# AD9236.net
KiCad netlist of a schematic drawn in Altium Designer
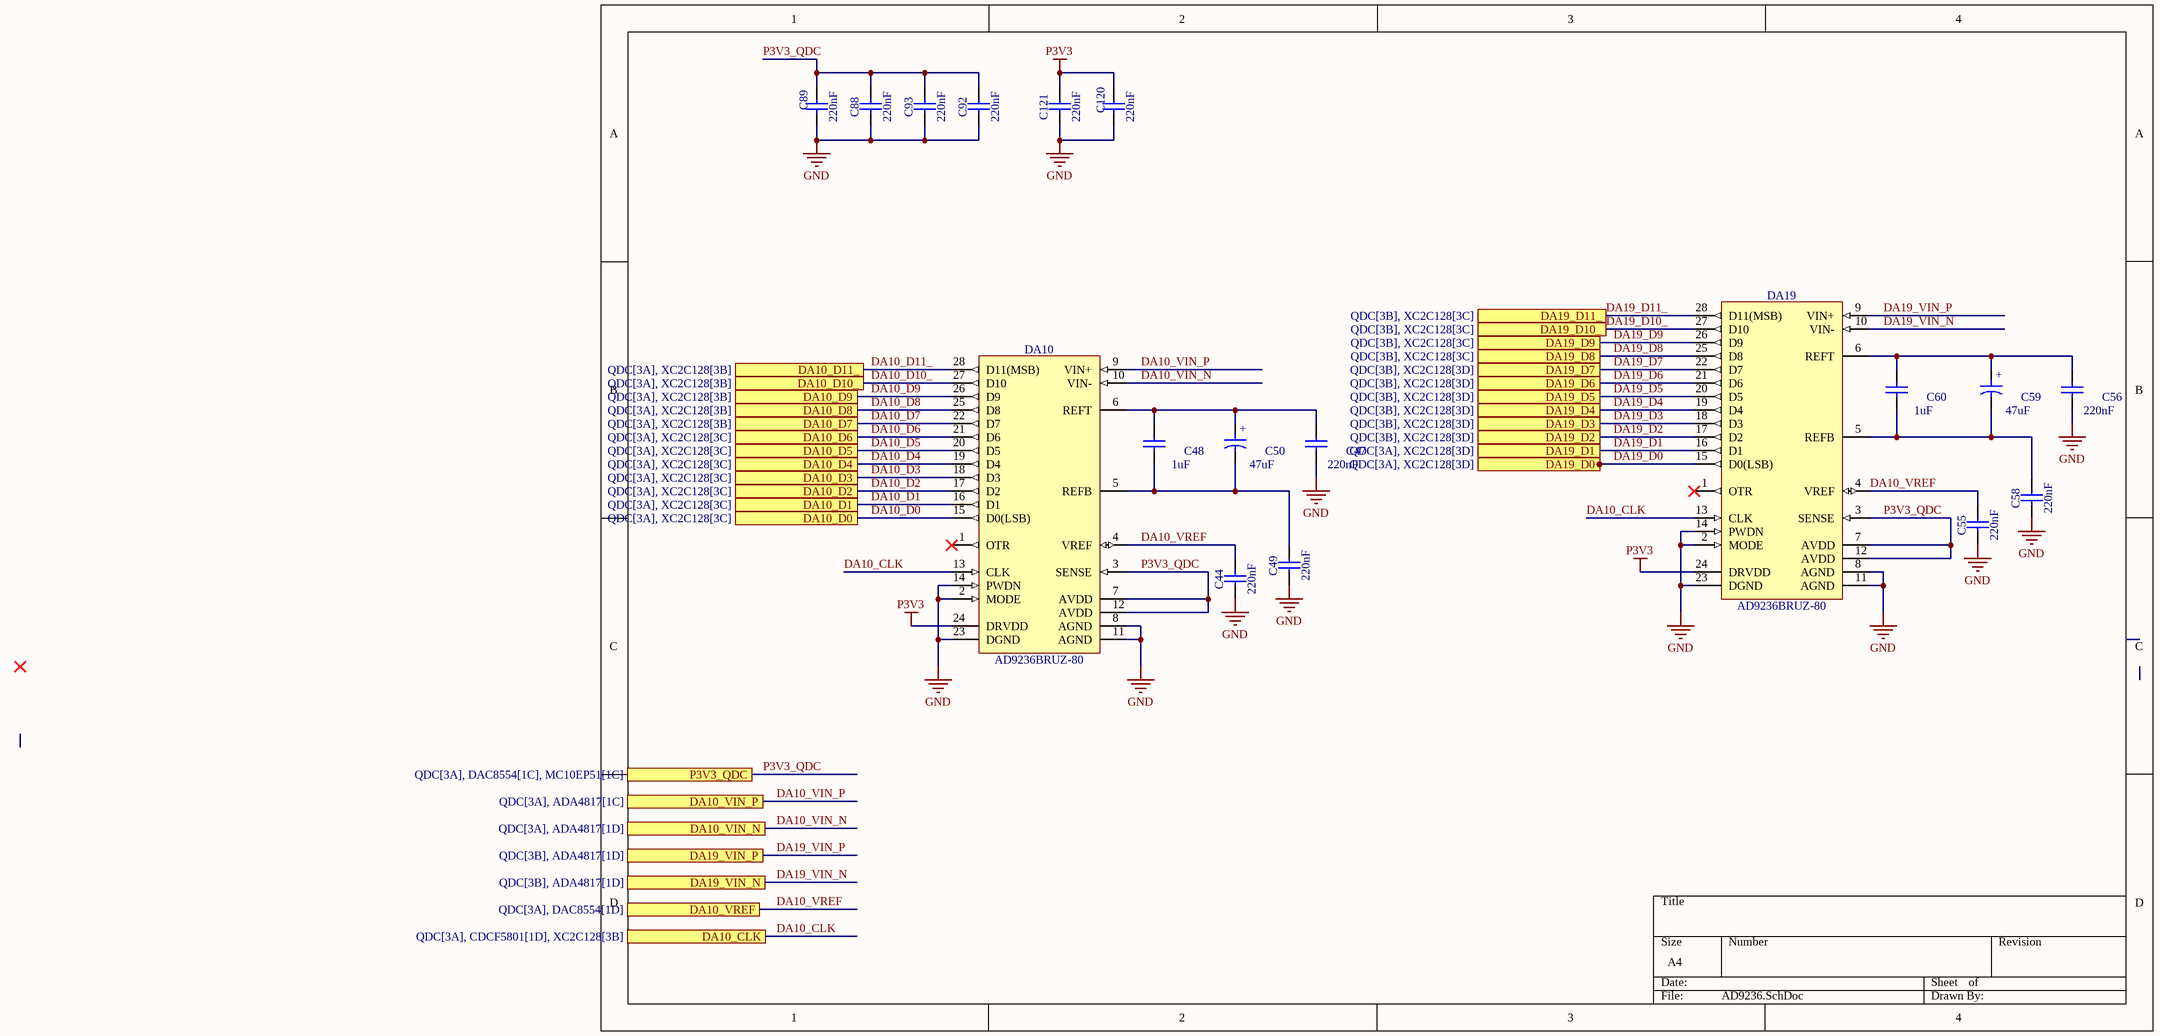
[diagram p0: AD9236.SchDoc]

(export (version "E")
  (design (tool "Eeschema 10.0.6"))
  (components
    (comp (ref "C44")
      (value "220nF")
      (footprint "CAPC2012X135N")
      (description "Non-polarised capacitor")
      (fields
        (field (name "PART NUMBER") "CC0805_220NF_50V_10%_X7R")
        (field (name "VOLTAGE") "50V")
        (field (name "AUTHOR") "CERN DEM JLC")
      )
      (libsource (lib "Capacitors") (part "Capacitor - non polarized"))
    )
    (comp (ref "C47")
      (value "220nF")
      (footprint "CAPC2012X135N")
      (description "Non-polarised capacitor")
      (fields
        (field (name "PART NUMBER") "CC0805_220NF_50V_10%_X7R")
        (field (name "VOLTAGE") "50V")
        (field (name "AUTHOR") "CERN DEM JLC")
      )
      (libsource (lib "Capacitors") (part "Capacitor - non polarized"))
    )
    (comp (ref "C48")
      (value "1uF")
      (footprint "CAPC2012X140N")
      (description "Non-polarised capacitor")
      (fields
        (field (name "PART NUMBER") "CC0805_1UF_25V_10%_X7R")
        (field (name "VOLTAGE") "25V")
        (field (name "AUTHOR") "CERN DEM JLC")
      )
      (libsource (lib "Capacitors") (part "Capacitor - non polarized"))
    )
    (comp (ref "C49")
      (value "220nF")
      (footprint "CAPC2012X135N")
      (description "Non-polarised capacitor")
      (fields
        (field (name "PART NUMBER") "CC0805_220NF_50V_10%_X7R")
        (field (name "VOLTAGE") "50V")
        (field (name "AUTHOR") "CERN DEM JLC")
      )
      (libsource (lib "Capacitors") (part "Capacitor - non polarized"))
    )
    (comp (ref "C50")
      (value "47uF")
      (footprint "CAPMP3528X120N")
      (description "Polarised capacitor")
      (fields
        (field (name "PART NUMBER") "CTE3528-12_47UF_10V_20%_PANASONIC_TPG")
        (field (name "VOLTAGE") "10V")
        (field (name "AUTHOR") "CERN DEM JLC")
      )
      (libsource (lib "Capacitors") (part "Capacitor - polarized"))
    )
    (comp (ref "C55")
      (value "220nF")
      (footprint "CAPC2012X135N")
      (description "Non-polarised capacitor")
      (fields
        (field (name "PART NUMBER") "CC0805_220NF_50V_10%_X7R")
        (field (name "VOLTAGE") "50V")
        (field (name "AUTHOR") "CERN DEM JLC")
      )
      (libsource (lib "Capacitors") (part "Capacitor - non polarized"))
    )
    (comp (ref "C56")
      (value "220nF")
      (footprint "CAPC2012X135N")
      (description "Non-polarised capacitor")
      (fields
        (field (name "PART NUMBER") "CC0805_220NF_50V_10%_X7R")
        (field (name "VOLTAGE") "50V")
        (field (name "AUTHOR") "CERN DEM JLC")
      )
      (libsource (lib "Capacitors") (part "Capacitor - non polarized"))
    )
    (comp (ref "C58")
      (value "220nF")
      (footprint "CAPC2012X135N")
      (description "Non-polarised capacitor")
      (fields
        (field (name "PART NUMBER") "CC0805_220NF_50V_10%_X7R")
        (field (name "VOLTAGE") "50V")
        (field (name "AUTHOR") "CERN DEM JLC")
      )
      (libsource (lib "Capacitors") (part "Capacitor - non polarized"))
    )
    (comp (ref "C59")
      (value "47uF")
      (footprint "CAPMP3528X120N")
      (description "Polarised capacitor")
      (fields
        (field (name "PART NUMBER") "CTE3528-12_47UF_10V_20%_PANASONIC_TPG")
        (field (name "VOLTAGE") "10V")
        (field (name "AUTHOR") "CERN DEM JLC")
      )
      (libsource (lib "Capacitors") (part "Capacitor - polarized"))
    )
    (comp (ref "C60")
      (value "1uF")
      (footprint "CAPC2012X140N")
      (description "Non-polarised capacitor")
      (fields
        (field (name "PART NUMBER") "CC0805_1UF_25V_10%_X7R")
        (field (name "VOLTAGE") "25V")
        (field (name "AUTHOR") "CERN DEM JLC")
      )
      (libsource (lib "Capacitors") (part "Capacitor - non polarized"))
    )
    (comp (ref "C88")
      (value "220nF")
      (footprint "CAPC2012X135N")
      (description "Non-polarised capacitor")
      (fields
        (field (name "PART NUMBER") "CC0805_220NF_50V_10%_X7R")
        (field (name "VOLTAGE") "50V")
        (field (name "AUTHOR") "CERN DEM JLC")
      )
      (libsource (lib "Capacitors") (part "Capacitor - non polarized"))
    )
    (comp (ref "C89")
      (value "220nF")
      (footprint "CAPC2012X135N")
      (description "Non-polarised capacitor")
      (fields
        (field (name "PART NUMBER") "CC0805_220NF_50V_10%_X7R")
        (field (name "VOLTAGE") "50V")
        (field (name "AUTHOR") "CERN DEM JLC")
      )
      (libsource (lib "Capacitors") (part "Capacitor - non polarized"))
    )
    (comp (ref "C92")
      (value "220nF")
      (footprint "CAPC2012X135N")
      (description "Non-polarised capacitor")
      (fields
        (field (name "PART NUMBER") "CC0805_220NF_50V_10%_X7R")
        (field (name "VOLTAGE") "50V")
        (field (name "AUTHOR") "CERN DEM JLC")
      )
      (libsource (lib "Capacitors") (part "Capacitor - non polarized"))
    )
    (comp (ref "C93")
      (value "220nF")
      (footprint "CAPC2012X135N")
      (description "Non-polarised capacitor")
      (fields
        (field (name "PART NUMBER") "CC0805_220NF_50V_10%_X7R")
        (field (name "VOLTAGE") "50V")
        (field (name "AUTHOR") "CERN DEM JLC")
      )
      (libsource (lib "Capacitors") (part "Capacitor - non polarized"))
    )
    (comp (ref "C120")
      (value "220nF")
      (footprint "CAPC2012X135N")
      (description "Non-polarised capacitor")
      (fields
        (field (name "PART NUMBER") "CC0805_220NF_50V_10%_X7R")
        (field (name "VOLTAGE") "50V")
        (field (name "AUTHOR") "CERN DEM JLC")
      )
      (libsource (lib "Capacitors") (part "Capacitor - non polarized"))
    )
    (comp (ref "C121")
      (value "220nF")
      (footprint "CAPC2012X135N")
      (description "Non-polarised capacitor")
      (fields
        (field (name "PART NUMBER") "CC0805_220NF_50V_10%_X7R")
        (field (name "VOLTAGE") "50V")
        (field (name "AUTHOR") "CERN DEM JLC")
      )
      (libsource (lib "Capacitors") (part "Capacitor - non polarized"))
    )
    (comp (ref "DA10")
      (value "AD9236BRUZ-80")
      (footprint "SOP65P640X120-28N")
      (description "12-Bit, 80 MSPS 3 V ADC")
      (fields
        (field (name "MANUFACTURER") "ANALOG DEVICES")
        (field (name "MANUFACTURER PART NUMBER") "AD9235BRUZ-40")
        (field (name "AUTHOR") "CERN DEM HF")
      )
      (libsource (lib "ICs And Semiconductors") (part "AD9236BRU"))
    )
    (comp (ref "DA19")
      (value "AD9236BRUZ-80")
      (footprint "SOP65P640X120-28N")
      (description "12-Bit, 80 MSPS 3 V ADC")
      (fields
        (field (name "MANUFACTURER") "ANALOG DEVICES")
        (field (name "MANUFACTURER PART NUMBER") "AD9235BRUZ-40")
        (field (name "AUTHOR") "CERN DEM HF")
      )
      (libsource (lib "ICs And Semiconductors") (part "AD9236BRU"))
    )
  )
  (nets
    (net (code "1") (name "/DA10_CLK") (class "Default")
      (node (ref "DA10") (pin "13") (pinfunction "CLK_13") (pintype "input"))
      (node (ref "DA19") (pin "13") (pinfunction "CLK_13") (pintype "input"))
    )
    (net (code "2") (name "/DA10_D0") (class "Default")
      (node (ref "DA10") (pin "15") (pinfunction "D0(LSB)_15") (pintype "output"))
    )
    (net (code "3") (name "/DA10_D1") (class "Default")
      (node (ref "DA10") (pin "16") (pinfunction "D1_16") (pintype "output"))
    )
    (net (code "4") (name "/DA10_D2") (class "Default")
      (node (ref "DA10") (pin "17") (pinfunction "D2_17") (pintype "output"))
    )
    (net (code "5") (name "/DA10_D3") (class "Default")
      (node (ref "DA10") (pin "18") (pinfunction "D3_18") (pintype "output"))
    )
    (net (code "6") (name "/DA10_D4") (class "Default")
      (node (ref "DA10") (pin "19") (pinfunction "D4_19") (pintype "output"))
    )
    (net (code "7") (name "/DA10_D5") (class "Default")
      (node (ref "DA10") (pin "20") (pinfunction "D5_20") (pintype "output"))
    )
    (net (code "8") (name "/DA10_D6") (class "Default")
      (node (ref "DA10") (pin "21") (pinfunction "D6_21") (pintype "output"))
    )
    (net (code "9") (name "/DA10_D7") (class "Default")
      (node (ref "DA10") (pin "22") (pinfunction "D7_22") (pintype "output"))
    )
    (net (code "10") (name "/DA10_D8") (class "Default")
      (node (ref "DA10") (pin "25") (pinfunction "D8_25") (pintype "output"))
    )
    (net (code "11") (name "/DA10_D9") (class "Default")
      (node (ref "DA10") (pin "26") (pinfunction "D9_26") (pintype "output"))
    )
    (net (code "12") (name "/DA10_D10_") (class "Default")
      (node (ref "DA10") (pin "27") (pinfunction "D10_27") (pintype "output"))
    )
    (net (code "13") (name "/DA10_D11_") (class "Default")
      (node (ref "DA10") (pin "28") (pinfunction "D11(MSB)_28") (pintype "output"))
    )
    (net (code "14") (name "/DA10_VIN_N") (class "Default")
      (node (ref "DA10") (pin "10") (pinfunction "VIN-_10") (pintype "input"))
    )
    (net (code "15") (name "/DA10_VIN_P") (class "Default")
      (node (ref "DA10") (pin "9") (pinfunction "VIN+_9") (pintype "input"))
    )
    (net (code "16") (name "/DA10_VREF") (class "Default")
      (node (ref "C44") (pin "2") (pinfunction "2_2") (pintype "passive"))
      (node (ref "C55") (pin "2") (pinfunction "2_2") (pintype "passive"))
      (node (ref "DA10") (pin "4") (pinfunction "VREF_4") (pintype "bidirectional"))
      (node (ref "DA19") (pin "4") (pinfunction "VREF_4") (pintype "bidirectional"))
    )
    (net (code "17") (name "/DA19_D0") (class "Default")
      (node (ref "DA19") (pin "15") (pinfunction "D0(LSB)_15") (pintype "output"))
    )
    (net (code "18") (name "/DA19_D1") (class "Default")
      (node (ref "DA19") (pin "16") (pinfunction "D1_16") (pintype "output"))
    )
    (net (code "19") (name "/DA19_D2") (class "Default")
      (node (ref "DA19") (pin "17") (pinfunction "D2_17") (pintype "output"))
    )
    (net (code "20") (name "/DA19_D3") (class "Default")
      (node (ref "DA19") (pin "18") (pinfunction "D3_18") (pintype "output"))
    )
    (net (code "21") (name "/DA19_D4") (class "Default")
      (node (ref "DA19") (pin "19") (pinfunction "D4_19") (pintype "output"))
    )
    (net (code "22") (name "/DA19_D5") (class "Default")
      (node (ref "DA19") (pin "20") (pinfunction "D5_20") (pintype "output"))
    )
    (net (code "23") (name "/DA19_D6") (class "Default")
      (node (ref "DA19") (pin "21") (pinfunction "D6_21") (pintype "output"))
    )
    (net (code "24") (name "/DA19_D7") (class "Default")
      (node (ref "DA19") (pin "22") (pinfunction "D7_22") (pintype "output"))
    )
    (net (code "25") (name "/DA19_D8") (class "Default")
      (node (ref "DA19") (pin "25") (pinfunction "D8_25") (pintype "output"))
    )
    (net (code "26") (name "/DA19_D9") (class "Default")
      (node (ref "DA19") (pin "26") (pinfunction "D9_26") (pintype "output"))
    )
    (net (code "27") (name "/DA19_D10_") (class "Default")
      (node (ref "DA19") (pin "27") (pinfunction "D10_27") (pintype "output"))
    )
    (net (code "28") (name "/DA19_D11_") (class "Default")
      (node (ref "DA19") (pin "28") (pinfunction "D11(MSB)_28") (pintype "output"))
    )
    (net (code "29") (name "/DA19_VIN_N") (class "Default")
      (node (ref "DA19") (pin "10") (pinfunction "VIN-_10") (pintype "input"))
    )
    (net (code "30") (name "/DA19_VIN_P") (class "Default")
      (node (ref "DA19") (pin "9") (pinfunction "VIN+_9") (pintype "input"))
    )
    (net (code "31") (name "/P3V3_QDC") (class "Default")
      (node (ref "C88") (pin "2") (pinfunction "2_2") (pintype "passive"))
      (node (ref "C89") (pin "2") (pinfunction "2_2") (pintype "passive"))
      (node (ref "C92") (pin "2") (pinfunction "2_2") (pintype "passive"))
      (node (ref "C93") (pin "2") (pinfunction "2_2") (pintype "passive"))
      (node (ref "DA10") (pin "12") (pinfunction "AVDD_12") (pintype "power_in"))
      (node (ref "DA10") (pin "3") (pinfunction "SENSE_3") (pintype "input"))
      (node (ref "DA10") (pin "7") (pinfunction "AVDD_7") (pintype "power_in"))
      (node (ref "DA19") (pin "12") (pinfunction "AVDD_12") (pintype "power_in"))
      (node (ref "DA19") (pin "3") (pinfunction "SENSE_3") (pintype "input"))
      (node (ref "DA19") (pin "7") (pinfunction "AVDD_7") (pintype "power_in"))
    )
    (net (code "32") (name "GND") (class "Default")
      (node (ref "C120") (pin "1") (pinfunction "1_1") (pintype "passive"))
      (node (ref "C121") (pin "1") (pinfunction "1_1") (pintype "passive"))
      (node (ref "C44") (pin "1") (pinfunction "1_1") (pintype "passive"))
      (node (ref "C47") (pin "1") (pinfunction "1_1") (pintype "passive"))
      (node (ref "C49") (pin "1") (pinfunction "1_1") (pintype "passive"))
      (node (ref "C55") (pin "1") (pinfunction "1_1") (pintype "passive"))
      (node (ref "C56") (pin "1") (pinfunction "1_1") (pintype "passive"))
      (node (ref "C58") (pin "1") (pinfunction "1_1") (pintype "passive"))
      (node (ref "C88") (pin "1") (pinfunction "1_1") (pintype "passive"))
      (node (ref "C89") (pin "1") (pinfunction "1_1") (pintype "passive"))
      (node (ref "C92") (pin "1") (pinfunction "1_1") (pintype "passive"))
      (node (ref "C93") (pin "1") (pinfunction "1_1") (pintype "passive"))
      (node (ref "DA10") (pin "11") (pinfunction "AGND_11") (pintype "power_in"))
      (node (ref "DA10") (pin "14") (pinfunction "PWDN_14") (pintype "input"))
      (node (ref "DA10") (pin "2") (pinfunction "MODE_2") (pintype "input"))
      (node (ref "DA10") (pin "23") (pinfunction "DGND_23") (pintype "power_in"))
      (node (ref "DA10") (pin "8") (pinfunction "AGND_8") (pintype "power_in"))
      (node (ref "DA19") (pin "11") (pinfunction "AGND_11") (pintype "power_in"))
      (node (ref "DA19") (pin "14") (pinfunction "PWDN_14") (pintype "input"))
      (node (ref "DA19") (pin "2") (pinfunction "MODE_2") (pintype "input"))
      (node (ref "DA19") (pin "23") (pinfunction "DGND_23") (pintype "power_in"))
      (node (ref "DA19") (pin "8") (pinfunction "AGND_8") (pintype "power_in"))
    )
    (net (code "33") (name "Net-(DA10-REFB)") (class "Default")
      (node (ref "C48") (pin "1") (pinfunction "1_1") (pintype "passive"))
      (node (ref "C49") (pin "2") (pinfunction "2_2") (pintype "passive"))
      (node (ref "C50") (pin "2") (pinfunction "2_2") (pintype "passive"))
      (node (ref "DA10") (pin "5") (pinfunction "REFB_5") (pintype "passive"))
    )
    (net (code "34") (name "Net-(DA10-REFT)") (class "Default")
      (node (ref "C47") (pin "2") (pinfunction "2_2") (pintype "passive"))
      (node (ref "C48") (pin "2") (pinfunction "2_2") (pintype "passive"))
      (node (ref "C50") (pin "1") (pinfunction "1_1") (pintype "passive"))
      (node (ref "DA10") (pin "6") (pinfunction "REFT_6") (pintype "passive"))
    )
    (net (code "35") (name "Net-(DA19-REFB)") (class "Default")
      (node (ref "C58") (pin "2") (pinfunction "2_2") (pintype "passive"))
      (node (ref "C59") (pin "2") (pinfunction "2_2") (pintype "passive"))
      (node (ref "C60") (pin "1") (pinfunction "1_1") (pintype "passive"))
      (node (ref "DA19") (pin "5") (pinfunction "REFB_5") (pintype "passive"))
    )
    (net (code "36") (name "Net-(DA19-REFT)") (class "Default")
      (node (ref "C56") (pin "2") (pinfunction "2_2") (pintype "passive"))
      (node (ref "C59") (pin "1") (pinfunction "1_1") (pintype "passive"))
      (node (ref "C60") (pin "2") (pinfunction "2_2") (pintype "passive"))
      (node (ref "DA19") (pin "6") (pinfunction "REFT_6") (pintype "passive"))
    )
    (net (code "37") (name "P3V3") (class "Default")
      (node (ref "C120") (pin "2") (pinfunction "2_2") (pintype "passive"))
      (node (ref "C121") (pin "2") (pinfunction "2_2") (pintype "passive"))
      (node (ref "DA10") (pin "24") (pinfunction "DRVDD_24") (pintype "power_in"))
      (node (ref "DA19") (pin "24") (pinfunction "DRVDD_24") (pintype "power_in"))
    )
    (net (code "38") (name "unconnected-(DA10-OTR-Pad1)") (class "Default")
      (node (ref "DA10") (pin "1") (pinfunction "OTR_1") (pintype "output+no_connect"))
    )
    (net (code "39") (name "unconnected-(DA19-OTR-Pad1)") (class "Default")
      (node (ref "DA19") (pin "1") (pinfunction "OTR_1") (pintype "output+no_connect"))
    )
  )
)
